# power_amp.net
KiCad netlist of a schematic drawn in Altium Designer
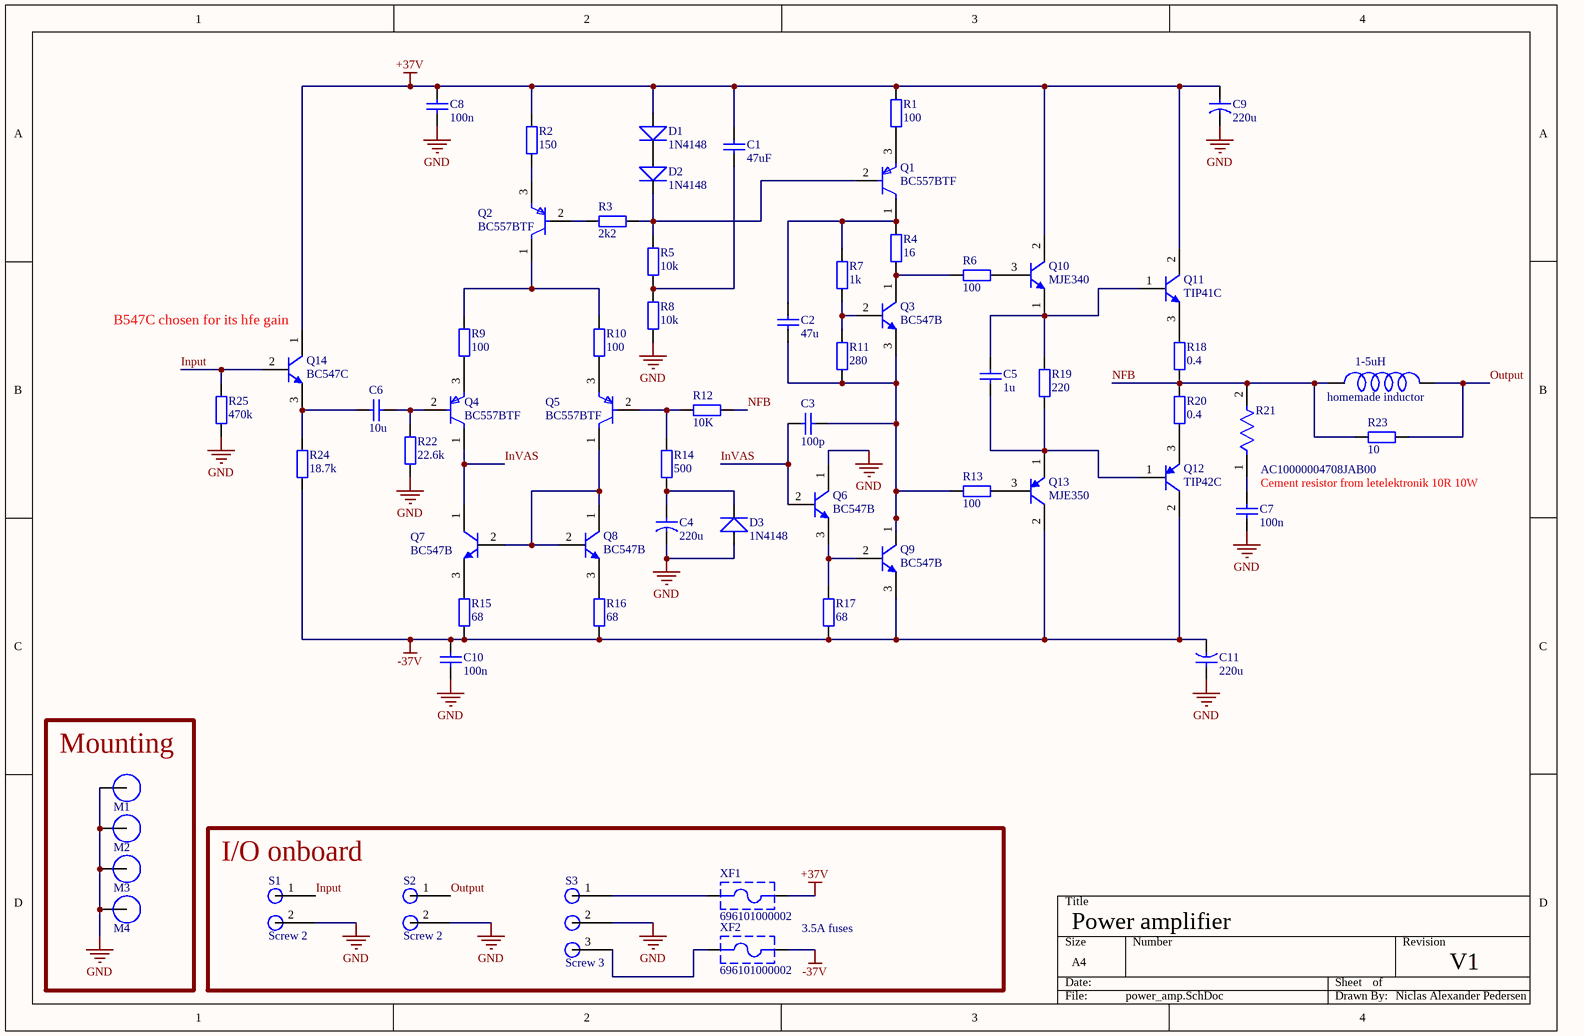
[diagram p0: power_amp.SchDoc]

(export (version "E")
  (design (tool "Eeschema 10.0.6"))
  (components
    (comp (ref "1-5uH")
      (value "homemade inductor")
      (footprint "homecooked inductor")
      (libsource (lib "esd410") (part "homemade inductor"))
    )
    (comp (ref "C1")
      (value "47uF")
      (footprint "Cap Ø8")
      (fields (field (name "Comment") "Cap"))
      (libsource (lib "AAURacing") (part "Capacitor unpolarized"))
    )
    (comp (ref "C2")
      (value "47u")
      (footprint "Cap Ø8")
      (fields (field (name "Comment") "Cap"))
      (libsource (lib "AAURacing") (part "Capacitor unpolarized"))
    )
    (comp (ref "C3")
      (value "100p")
      (footprint "Cap-1")
      (fields (field (name "Comment") "Cap"))
      (libsource (lib "AAURacing") (part "Capacitor 1 space"))
    )
    (comp (ref "C4")
      (value "220u")
      (footprint "Cap Lyt Ø8")
      (fields (field (name "Comment") "Cap"))
      (libsource (lib "AAURacing") (part "Capacitor electrolytic"))
    )
    (comp (ref "C5")
      (value "1u")
      (footprint "Cap Ø8")
      (fields (field (name "Comment") "Cap"))
      (libsource (lib "AAURacing") (part "Capacitor unpolarized"))
    )
    (comp (ref "C6")
      (value "10u")
      (footprint "Cap Ø8")
      (fields (field (name "Comment") "Cap"))
      (libsource (lib "AAURacing") (part "Capacitor unpolarized"))
    )
    (comp (ref "C7")
      (value "100n")
      (footprint "Cap Ø8")
      (fields (field (name "Comment") "Cap"))
      (libsource (lib "AAURacing") (part "Capacitor unpolarized"))
    )
    (comp (ref "C8")
      (value "100n")
      (footprint "Cap-1")
      (fields (field (name "Comment") "Cap"))
      (libsource (lib "AAURacing") (part "Capacitor 1 space"))
    )
    (comp (ref "C9")
      (value "220u")
      (footprint "Cap Lyt Ø8")
      (fields (field (name "Comment") "Cap"))
      (libsource (lib "AAURacing") (part "Capacitor electrolytic"))
    )
    (comp (ref "C10")
      (value "100n")
      (footprint "Cap-1")
      (fields (field (name "Comment") "Cap"))
      (libsource (lib "AAURacing") (part "Capacitor 1 space"))
    )
    (comp (ref "C11")
      (value "220u")
      (footprint "Cap Lyt Ø8")
      (fields (field (name "Comment") "Cap"))
      (libsource (lib "AAURacing") (part "Capacitor electrolytic"))
    )
    (comp (ref "D1")
      (value "Diode DO-35")
      (footprint "Diode 2 space")
      (fields (field (name "MODEL") "1N4148"))
      (libsource (lib "AAURacing") (part "Diode DO-35"))
    )
    (comp (ref "D2")
      (value "Diode DO-35")
      (footprint "Diode 2 space")
      (fields (field (name "MODEL") "1N4148"))
      (libsource (lib "AAURacing") (part "Diode DO-35"))
    )
    (comp (ref "D3")
      (value "Diode DO-35")
      (footprint "Diode 2 space")
      (fields (field (name "MODEL") "1N4148"))
      (libsource (lib "AAURacing") (part "Diode DO-35"))
    )
    (comp (ref "M1")
      (value "Screw Hole")
      (footprint "M3 Hole")
      (libsource (lib "AAURacing") (part "Screw Hole"))
    )
    (comp (ref "M2")
      (value "Screw Hole")
      (footprint "M3 Hole")
      (libsource (lib "AAURacing") (part "Screw Hole"))
    )
    (comp (ref "M3")
      (value "Screw Hole")
      (footprint "M3 Hole")
      (libsource (lib "AAURacing") (part "Screw Hole"))
    )
    (comp (ref "M4")
      (value "Screw Hole")
      (footprint "M3 Hole")
      (libsource (lib "AAURacing") (part "Screw Hole"))
    )
    (comp (ref "Q1")
      (value "BC557BTF")
      (footprint "FP-135AR-MFG")
      (description "BC557BTF Small Signal Bipolar Transistor, 0.1A I(C), 45V V(BR)CEO, 1-Element, PNP, Silicon, TO-92")
      (libsource (lib "Altium Content Vault") (part "9e2844d3eb996af6824d2c99fe21afc"))
    )
    (comp (ref "Q2")
      (value "BC557BTF")
      (footprint "FP-135AR-MFG")
      (description "BC557BTF Small Signal Bipolar Transistor, 0.1A I(C), 45V V(BR)CEO, 1-Element, PNP, Silicon, TO-92")
      (libsource (lib "Altium Content Vault") (part "9e2844d3eb996af6824d2c99fe21afc"))
    )
    (comp (ref "Q3")
      (value "BC547B")
      (footprint "ONSC-TO-92-3-29-11")
      (description "Amplifier Transistor, NPN Silicon, 3-Pin TO-92, Bulk Box")
      (fields (field (name "MANUFACTURER") "On Semiconductor"))
      (libsource (lib "Altium Content Vault") (part "ONSC-NPN-C1B2E3-3"))
    )
    (comp (ref "Q4")
      (value "BC557BTF")
      (footprint "FP-135AR-MFG")
      (description "BC557BTF Small Signal Bipolar Transistor, 0.1A I(C), 45V V(BR)CEO, 1-Element, PNP, Silicon, TO-92")
      (libsource (lib "Altium Content Vault") (part "9e2844d3eb996af6824d2c99fe21afc"))
    )
    (comp (ref "Q5")
      (value "BC557BTF")
      (footprint "FP-135AR-MFG")
      (description "BC557BTF Small Signal Bipolar Transistor, 0.1A I(C), 45V V(BR)CEO, 1-Element, PNP, Silicon, TO-92")
      (libsource (lib "Altium Content Vault") (part "9e2844d3eb996af6824d2c99fe21afc"))
    )
    (comp (ref "Q6")
      (value "BC547B")
      (footprint "ONSC-TO-92-3-29-11")
      (description "Amplifier Transistor, NPN Silicon, 3-Pin TO-92, Bulk Box")
      (fields (field (name "MANUFACTURER") "On Semiconductor"))
      (libsource (lib "Altium Content Vault") (part "ONSC-NPN-C1B2E3-3"))
    )
    (comp (ref "Q7")
      (value "BC547B")
      (footprint "ONSC-TO-92-3-29-11")
      (description "Amplifier Transistor, NPN Silicon, 3-Pin TO-92, Bulk Box")
      (fields (field (name "MANUFACTURER") "On Semiconductor"))
      (libsource (lib "Altium Content Vault") (part "ONSC-NPN-C1B2E3-3"))
    )
    (comp (ref "Q8")
      (value "BC547B")
      (footprint "ONSC-TO-92-3-29-11")
      (description "Amplifier Transistor, NPN Silicon, 3-Pin TO-92, Bulk Box")
      (fields (field (name "MANUFACTURER") "On Semiconductor"))
      (libsource (lib "Altium Content Vault") (part "ONSC-NPN-C1B2E3-3"))
    )
    (comp (ref "Q9")
      (value "BC547B")
      (footprint "ONSC-TO-92-3-29-11")
      (description "Amplifier Transistor, NPN Silicon, 3-Pin TO-92, Bulk Box")
      (fields (field (name "MANUFACTURER") "On Semiconductor"))
      (libsource (lib "Altium Content Vault") (part "ONSC-NPN-C1B2E3-3"))
    )
    (comp (ref "Q10")
      (value "MJE340")
      (footprint "ONSC-TO-225-3-77-09")
      (description "Plastic Medium-Power NPN Silicon Transistor, 3-Pin TO-225, Bulk Box")
      (fields (field (name "MANUFACTURER") "On Semiconductor"))
      (libsource (lib "Altium Content Vault") (part "ONSC-NPN-E1C2B3-3"))
    )
    (comp (ref "Q11")
      (value "TIP41C")
      (footprint "ONSC-TO-220-3-221A-09")
      (description "Complementary Silicon Plastic Power Transistor, 3-Pin TO-220, Tube")
      (fields (field (name "MANUFACTURER") "On Semiconductor"))
      (libsource (lib "Altium Content Vault") (part "ONSC-NPN-B1C2E3-3_C"))
    )
    (comp (ref "Q12")
      (value "TIP42C")
      (footprint "ONSC-TO-220-3-221A-09")
      (description "Complementary Silicon Plastic Power Transistor, 3-Pin TO-220, Tube")
      (fields (field (name "MANUFACTURER") "On Semiconductor"))
      (libsource (lib "Altium Content Vault") (part "ONSC-PNP-B1C2E3-3"))
    )
    (comp (ref "Q13")
      (value "MJE350")
      (footprint "ONSC-TO-225-3-77-09")
      (description "Plastic Medium-Power PNP Silicon Transistor, 3-Pin TO-225, Bulk Box")
      (fields (field (name "MANUFACTURER") "On Semiconductor"))
      (libsource (lib "Altium Content Vault") (part "ONSC-PNP-E1C2B3-3"))
    )
    (comp (ref "Q14")
      (value "BC547C")
      (footprint "ONSC-TO-92-3-29-11")
      (description "Amplifier Transistor, NPN Silicon, 3-Pin TO-92, Bulk Box")
      (fields (field (name "MANUFACTURER") "On Semiconductor") (field (name "PARTNUMBER") "BC547B"))
      (libsource (lib "Altium Content Vault") (part "ONSC-NPN-C1B2E3-3"))
    )
    (comp (ref "R1")
      (value "100")
      (footprint "RES THT 9mm")
      (fields (field (name "Comment") "Resistor"))
      (libsource (lib "AAURacing") (part "Resistor"))
    )
    (comp (ref "R2")
      (value "150")
      (footprint "RES THT 9mm")
      (fields (field (name "Comment") "Resistor"))
      (libsource (lib "AAURacing") (part "Resistor"))
    )
    (comp (ref "R3")
      (value "2k2")
      (footprint "RES THT 9mm")
      (fields (field (name "Comment") "Resistor"))
      (libsource (lib "AAURacing") (part "Resistor"))
    )
    (comp (ref "R4")
      (value "16")
      (footprint "RES THT 9mm")
      (fields (field (name "Comment") "Resistor"))
      (libsource (lib "AAURacing") (part "Resistor"))
    )
    (comp (ref "R5")
      (value "10k")
      (footprint "RES THT 9mm")
      (fields (field (name "Comment") "Resistor"))
      (libsource (lib "AAURacing") (part "Resistor"))
    )
    (comp (ref "R6")
      (value "100")
      (footprint "RES THT 9mm")
      (fields (field (name "Comment") "Resistor"))
      (libsource (lib "AAURacing") (part "Resistor"))
    )
    (comp (ref "R7")
      (value "1k")
      (footprint "RES THT 9mm")
      (fields (field (name "Comment") "Resistor"))
      (libsource (lib "AAURacing") (part "Resistor"))
    )
    (comp (ref "R8")
      (value "10k")
      (footprint "RES THT 9mm")
      (fields (field (name "Comment") "Resistor"))
      (libsource (lib "AAURacing") (part "Resistor"))
    )
    (comp (ref "R9")
      (value "100")
      (footprint "RES THT 9mm")
      (fields (field (name "Comment") "Resistor"))
      (libsource (lib "AAURacing") (part "Resistor"))
    )
    (comp (ref "R10")
      (value "100")
      (footprint "RES THT 9mm")
      (fields (field (name "Comment") "Resistor"))
      (libsource (lib "AAURacing") (part "Resistor"))
    )
    (comp (ref "R11")
      (value "280")
      (footprint "RES THT 9mm")
      (fields (field (name "Comment") "Resistor"))
      (libsource (lib "AAURacing") (part "Resistor"))
    )
    (comp (ref "R12")
      (value "10K")
      (footprint "RES THT 9mm")
      (fields (field (name "Comment") "Resistor"))
      (libsource (lib "AAURacing") (part "Resistor"))
    )
    (comp (ref "R13")
      (value "100")
      (footprint "RES THT 9mm")
      (fields (field (name "Comment") "Resistor"))
      (libsource (lib "AAURacing") (part "Resistor"))
    )
    (comp (ref "R14")
      (value "500")
      (footprint "RES THT 9mm")
      (fields (field (name "Comment") "Resistor"))
      (libsource (lib "AAURacing") (part "Resistor"))
    )
    (comp (ref "R15")
      (value "68")
      (footprint "RES THT 9mm")
      (fields (field (name "Comment") "Resistor"))
      (libsource (lib "AAURacing") (part "Resistor"))
    )
    (comp (ref "R16")
      (value "68")
      (footprint "RES THT 9mm")
      (fields (field (name "Comment") "Resistor"))
      (libsource (lib "AAURacing") (part "Resistor"))
    )
    (comp (ref "R17")
      (value "68")
      (footprint "RES THT 9mm")
      (fields (field (name "Comment") "Resistor"))
      (libsource (lib "AAURacing") (part "Resistor"))
    )
    (comp (ref "R18")
      (value "0.4")
      (footprint "RES THT 30mm")
      (fields (field (name "Comment") "Resistor"))
      (libsource (lib "AAURacing") (part "Resistor"))
    )
    (comp (ref "R19")
      (value "220")
      (footprint "RES THT 9mm")
      (fields (field (name "Comment") "Resistor"))
      (libsource (lib "AAURacing") (part "Resistor"))
    )
    (comp (ref "R20")
      (value "0.4")
      (footprint "RES THT 30mm")
      (fields (field (name "Comment") "Resistor"))
      (libsource (lib "AAURacing") (part "Resistor"))
    )
    (comp (ref "R21")
      (value "AC10000004708JAB00")
      (footprint "FP-AC10-MFG")
      (description "AC10000004708JAB00 Resistor, 4.7 Ohm, ± 5%, 10 W, Axial Leaded, Wirewound, General Purpose")
      (fields (field (name "TOLERANCE") "5%"))
      (libsource (lib "Altium Content Vault") (part "1029c3af85768c4190bb7ad29bc67b5"))
    )
    (comp (ref "R22")
      (value "22.6k")
      (footprint "RES THT 9mm")
      (fields (field (name "Comment") "Resistor"))
      (libsource (lib "AAURacing") (part "Resistor"))
    )
    (comp (ref "R23")
      (value "10")
      (footprint "RES THT 9mm")
      (fields (field (name "Comment") "Resistor"))
      (libsource (lib "AAURacing") (part "Resistor"))
    )
    (comp (ref "R24")
      (value "18.7k")
      (footprint "RES THT 9mm")
      (fields (field (name "Comment") "Resistor"))
      (libsource (lib "AAURacing") (part "Resistor"))
    )
    (comp (ref "R25")
      (value "470k")
      (footprint "RES THT 9mm")
      (fields (field (name "Comment") "Resistor"))
      (libsource (lib "AAURacing") (part "Resistor"))
    )
    (comp (ref "S1") (value "Screw 2") (footprint "Screw-2") (libsource (lib "AAURacing") (part "Screw 2")))
    (comp (ref "S2") (value "Screw 2") (footprint "Screw-2") (libsource (lib "AAURacing") (part "Screw 2")))
    (comp (ref "S3") (value "Screw 3") (footprint "Screw-3") (libsource (lib "AAURacing") (part "Screw 3")))
    (comp (ref "XF1")
      (value "696101000002")
      (footprint "696101000002")
      (libsource (lib "Altium Content Vault") (part "Fuse Holder"))
    )
    (comp (ref "XF2")
      (value "696101000002")
      (footprint "696101000002")
      (libsource (lib "Altium Content Vault") (part "Fuse Holder"))
    )
  )
  (nets
    (net (code "1") (name "+37V") (class "Default")
      (node (ref "C1") (pin "2") (pinfunction "g_2") (pintype "passive"))
      (node (ref "C8") (pin "2") (pinfunction "g_2") (pintype "passive"))
      (node (ref "C9") (pin "1") (pinfunction "1_1") (pintype "passive"))
      (node (ref "D1") (pin "1") (pinfunction "1_1") (pintype "passive"))
      (node (ref "Q10") (pin "2") (pinfunction "C_2") (pintype "passive"))
      (node (ref "Q11") (pin "2") (pinfunction "C_2") (pintype "passive"))
      (node (ref "Q14") (pin "1") (pinfunction "C_1") (pintype "passive"))
      (node (ref "R1") (pin "2") (pinfunction "2_2") (pintype "passive"))
      (node (ref "R2") (pin "2") (pinfunction "2_2") (pintype "passive"))
      (node (ref "XF1") (pin "2") (pinfunction "2_2") (pintype "passive"))
    )
    (net (code "2") (name "-37V") (class "Default")
      (node (ref "C10") (pin "2") (pinfunction "g_2") (pintype "passive"))
      (node (ref "C11") (pin "2") (pinfunction "g_2") (pintype "passive"))
      (node (ref "Q12") (pin "2") (pinfunction "C_2") (pintype "passive"))
      (node (ref "Q13") (pin "2") (pinfunction "C_2") (pintype "passive"))
      (node (ref "Q9") (pin "3") (pinfunction "E_3") (pintype "passive"))
      (node (ref "R15") (pin "1") (pinfunction "1_1") (pintype "passive"))
      (node (ref "R16") (pin "1") (pinfunction "1_1") (pintype "passive"))
      (node (ref "R17") (pin "1") (pinfunction "1_1") (pintype "passive"))
      (node (ref "R24") (pin "2") (pinfunction "2_2") (pintype "passive"))
      (node (ref "XF2") (pin "2") (pinfunction "2_2") (pintype "passive"))
    )
    (net (code "3") (name "/InVAS") (class "Default")
      (node (ref "C3") (pin "1") (pinfunction "1_1") (pintype "passive"))
      (node (ref "Q4") (pin "1") (pinfunction "C_1") (pintype "passive"))
      (node (ref "Q6") (pin "2") (pinfunction "B_2") (pintype "passive"))
      (node (ref "Q7") (pin "1") (pinfunction "C_1") (pintype "passive"))
    )
    (net (code "4") (name "/Input") (class "Default")
      (node (ref "Q14") (pin "2") (pinfunction "B_2") (pintype "passive"))
      (node (ref "R25") (pin "2") (pinfunction "2_2") (pintype "passive"))
      (node (ref "S1") (pin "1") (pinfunction "1_1") (pintype "passive"))
    )
    (net (code "5") (name "/NFB") (class "Default")
      (node (ref "1-5uH") (pin "1") (pintype "passive"))
      (node (ref "R12") (pin "1") (pinfunction "1_1") (pintype "passive"))
      (node (ref "R18") (pin "1") (pinfunction "1_1") (pintype "passive"))
      (node (ref "R20") (pin "2") (pinfunction "2_2") (pintype "passive"))
      (node (ref "R21") (pin "2") (pinfunction "2_2") (pintype "passive"))
      (node (ref "R23") (pin "2") (pinfunction "2_2") (pintype "passive"))
    )
    (net (code "6") (name "/Output") (class "Default")
      (node (ref "1-5uH") (pin "2") (pintype "passive"))
      (node (ref "R23") (pin "1") (pinfunction "1_1") (pintype "passive"))
      (node (ref "S2") (pin "1") (pinfunction "1_1") (pintype "passive"))
    )
    (net (code "7") (name "GND") (class "Default")
      (node (ref "C10") (pin "1") (pinfunction "1_1") (pintype "passive"))
      (node (ref "C11") (pin "1") (pinfunction "1_1") (pintype "passive"))
      (node (ref "C4") (pin "2") (pinfunction "g_2") (pintype "passive"))
      (node (ref "C7") (pin "1") (pinfunction "1_1") (pintype "passive"))
      (node (ref "C8") (pin "1") (pinfunction "1_1") (pintype "passive"))
      (node (ref "C9") (pin "2") (pinfunction "g_2") (pintype "passive"))
      (node (ref "D3") (pin "1") (pinfunction "1_1") (pintype "passive"))
      (node (ref "M1") (pin "1") (pinfunction "1_1") (pintype "passive"))
      (node (ref "M2") (pin "1") (pinfunction "1_1") (pintype "passive"))
      (node (ref "M3") (pin "1") (pinfunction "1_1") (pintype "passive"))
      (node (ref "M4") (pin "1") (pinfunction "1_1") (pintype "passive"))
      (node (ref "Q6") (pin "1") (pinfunction "C_1") (pintype "passive"))
      (node (ref "R22") (pin "2") (pinfunction "2_2") (pintype "passive"))
      (node (ref "R25") (pin "1") (pinfunction "1_1") (pintype "passive"))
      (node (ref "R8") (pin "2") (pinfunction "2_2") (pintype "passive"))
      (node (ref "S1") (pin "2") (pinfunction "2_2") (pintype "passive"))
      (node (ref "S2") (pin "2") (pinfunction "2_2") (pintype "passive"))
      (node (ref "S3") (pin "2") (pinfunction "2_2") (pintype "passive"))
    )
    (net (code "8") (name "Net-(C1-Pad1)") (class "Default")
      (node (ref "C1") (pin "1") (pinfunction "1_1") (pintype "passive"))
      (node (ref "R5") (pin "2") (pinfunction "2_2") (pintype "passive"))
      (node (ref "R8") (pin "1") (pinfunction "1_1") (pintype "passive"))
    )
    (net (code "9") (name "Net-(C2-g)") (class "Default")
      (node (ref "C2") (pin "2") (pinfunction "g_2") (pintype "passive"))
      (node (ref "Q1") (pin "1") (pinfunction "C_1") (pintype "passive"))
      (node (ref "R4") (pin "2") (pinfunction "2_2") (pintype "passive"))
      (node (ref "R7") (pin "2") (pinfunction "2_2") (pintype "passive"))
    )
    (net (code "10") (name "Net-(C3-g)") (class "Default")
      (node (ref "C2") (pin "1") (pinfunction "1_1") (pintype "passive"))
      (node (ref "C3") (pin "2") (pinfunction "g_2") (pintype "passive"))
      (node (ref "Q3") (pin "3") (pinfunction "E_3") (pintype "passive"))
      (node (ref "Q9") (pin "1") (pinfunction "C_1") (pintype "passive"))
      (node (ref "R11") (pin "1") (pinfunction "1_1") (pintype "passive"))
      (node (ref "R13") (pin "2") (pinfunction "2_2") (pintype "passive"))
    )
    (net (code "11") (name "Net-(C4-Pad1)") (class "Default")
      (node (ref "C4") (pin "1") (pinfunction "1_1") (pintype "passive"))
      (node (ref "D3") (pin "2") (pinfunction "2_2") (pintype "passive"))
      (node (ref "R14") (pin "1") (pinfunction "1_1") (pintype "passive"))
    )
    (net (code "12") (name "Net-(C5-g)") (class "Default")
      (node (ref "C5") (pin "2") (pinfunction "g_2") (pintype "passive"))
      (node (ref "Q10") (pin "1") (pinfunction "E_1") (pintype "passive"))
      (node (ref "Q11") (pin "1") (pinfunction "B_1") (pintype "passive"))
      (node (ref "R19") (pin "2") (pinfunction "2_2") (pintype "passive"))
    )
    (net (code "13") (name "Net-(C6-g)") (class "Default")
      (node (ref "C6") (pin "2") (pinfunction "g_2") (pintype "passive"))
      (node (ref "Q14") (pin "3") (pinfunction "E_3") (pintype "passive"))
      (node (ref "R24") (pin "1") (pinfunction "1_1") (pintype "passive"))
    )
    (net (code "14") (name "Net-(C7-g)") (class "Default")
      (node (ref "C7") (pin "2") (pinfunction "g_2") (pintype "passive"))
      (node (ref "R21") (pin "1") (pinfunction "1_1") (pintype "passive"))
    )
    (net (code "15") (name "Net-(D1-Pad2)") (class "Default")
      (node (ref "D1") (pin "2") (pinfunction "2_2") (pintype "passive"))
      (node (ref "D2") (pin "1") (pinfunction "1_1") (pintype "passive"))
    )
    (net (code "16") (name "Net-(Q1-B)") (class "Default")
      (node (ref "D2") (pin "2") (pinfunction "2_2") (pintype "passive"))
      (node (ref "Q1") (pin "2") (pinfunction "B_2") (pintype "passive"))
      (node (ref "R3") (pin "1") (pinfunction "1_1") (pintype "passive"))
      (node (ref "R5") (pin "1") (pinfunction "1_1") (pintype "passive"))
    )
    (net (code "17") (name "Net-(Q1-E)") (class "Default")
      (node (ref "Q1") (pin "3") (pinfunction "E_3") (pintype "passive"))
      (node (ref "R1") (pin "1") (pinfunction "1_1") (pintype "passive"))
    )
    (net (code "18") (name "Net-(Q2-B)") (class "Default")
      (node (ref "Q2") (pin "2") (pinfunction "B_2") (pintype "passive"))
      (node (ref "R3") (pin "2") (pinfunction "2_2") (pintype "passive"))
    )
    (net (code "19") (name "Net-(Q2-C)") (class "Default")
      (node (ref "Q2") (pin "1") (pinfunction "C_1") (pintype "passive"))
      (node (ref "R10") (pin "2") (pinfunction "2_2") (pintype "passive"))
      (node (ref "R9") (pin "2") (pinfunction "2_2") (pintype "passive"))
    )
    (net (code "20") (name "Net-(Q2-E)") (class "Default")
      (node (ref "Q2") (pin "3") (pinfunction "E_3") (pintype "passive"))
      (node (ref "R2") (pin "1") (pinfunction "1_1") (pintype "passive"))
    )
    (net (code "21") (name "Net-(Q3-B)") (class "Default")
      (node (ref "Q3") (pin "2") (pinfunction "B_2") (pintype "passive"))
      (node (ref "R11") (pin "2") (pinfunction "2_2") (pintype "passive"))
      (node (ref "R7") (pin "1") (pinfunction "1_1") (pintype "passive"))
    )
    (net (code "22") (name "Net-(Q3-C)") (class "Default")
      (node (ref "Q3") (pin "1") (pinfunction "C_1") (pintype "passive"))
      (node (ref "R4") (pin "1") (pinfunction "1_1") (pintype "passive"))
      (node (ref "R6") (pin "2") (pinfunction "2_2") (pintype "passive"))
    )
    (net (code "23") (name "Net-(Q4-B)") (class "Default")
      (node (ref "C6") (pin "1") (pinfunction "1_1") (pintype "passive"))
      (node (ref "Q4") (pin "2") (pinfunction "B_2") (pintype "passive"))
      (node (ref "R22") (pin "1") (pinfunction "1_1") (pintype "passive"))
    )
    (net (code "24") (name "Net-(Q4-E)") (class "Default")
      (node (ref "Q4") (pin "3") (pinfunction "E_3") (pintype "passive"))
      (node (ref "R9") (pin "1") (pinfunction "1_1") (pintype "passive"))
    )
    (net (code "25") (name "Net-(Q5-B)") (class "Default")
      (node (ref "Q5") (pin "2") (pinfunction "B_2") (pintype "passive"))
      (node (ref "R12") (pin "2") (pinfunction "2_2") (pintype "passive"))
      (node (ref "R14") (pin "2") (pinfunction "2_2") (pintype "passive"))
    )
    (net (code "26") (name "Net-(Q5-C)") (class "Default")
      (node (ref "Q5") (pin "1") (pinfunction "C_1") (pintype "passive"))
      (node (ref "Q7") (pin "2") (pinfunction "B_2") (pintype "passive"))
      (node (ref "Q8") (pin "1") (pinfunction "C_1") (pintype "passive"))
      (node (ref "Q8") (pin "2") (pinfunction "B_2") (pintype "passive"))
    )
    (net (code "27") (name "Net-(Q5-E)") (class "Default")
      (node (ref "Q5") (pin "3") (pinfunction "E_3") (pintype "passive"))
      (node (ref "R10") (pin "1") (pinfunction "1_1") (pintype "passive"))
    )
    (net (code "28") (name "Net-(Q6-E)") (class "Default")
      (node (ref "Q6") (pin "3") (pinfunction "E_3") (pintype "passive"))
      (node (ref "Q9") (pin "2") (pinfunction "B_2") (pintype "passive"))
      (node (ref "R17") (pin "2") (pinfunction "2_2") (pintype "passive"))
    )
    (net (code "29") (name "Net-(Q7-E)") (class "Default")
      (node (ref "Q7") (pin "3") (pinfunction "E_3") (pintype "passive"))
      (node (ref "R15") (pin "2") (pinfunction "2_2") (pintype "passive"))
    )
    (net (code "30") (name "Net-(Q8-E)") (class "Default")
      (node (ref "Q8") (pin "3") (pinfunction "E_3") (pintype "passive"))
      (node (ref "R16") (pin "2") (pinfunction "2_2") (pintype "passive"))
    )
    (net (code "31") (name "Net-(Q10-B)") (class "Default")
      (node (ref "Q10") (pin "3") (pinfunction "B_3") (pintype "passive"))
      (node (ref "R6") (pin "1") (pinfunction "1_1") (pintype "passive"))
    )
    (net (code "32") (name "Net-(Q11-E)") (class "Default")
      (node (ref "Q11") (pin "3") (pinfunction "E_3") (pintype "passive"))
      (node (ref "R18") (pin "2") (pinfunction "2_2") (pintype "passive"))
    )
    (net (code "33") (name "Net-(Q12-B)") (class "Default")
      (node (ref "C5") (pin "1") (pinfunction "1_1") (pintype "passive"))
      (node (ref "Q12") (pin "1") (pinfunction "B_1") (pintype "passive"))
      (node (ref "Q13") (pin "1") (pinfunction "E_1") (pintype "passive"))
      (node (ref "R19") (pin "1") (pinfunction "1_1") (pintype "passive"))
    )
    (net (code "34") (name "Net-(Q12-E)") (class "Default")
      (node (ref "Q12") (pin "3") (pinfunction "E_3") (pintype "passive"))
      (node (ref "R20") (pin "1") (pinfunction "1_1") (pintype "passive"))
    )
    (net (code "35") (name "Net-(Q13-B)") (class "Default")
      (node (ref "Q13") (pin "3") (pinfunction "B_3") (pintype "passive"))
      (node (ref "R13") (pin "1") (pinfunction "1_1") (pintype "passive"))
    )
    (net (code "36") (name "Net-(S3-Pad1)") (class "Default")
      (node (ref "S3") (pin "1") (pinfunction "1_1") (pintype "passive"))
      (node (ref "XF1") (pin "1") (pinfunction "1_1") (pintype "passive"))
    )
    (net (code "37") (name "Net-(S3-Pad3)") (class "Default")
      (node (ref "S3") (pin "3") (pinfunction "3_3") (pintype "passive"))
      (node (ref "XF2") (pin "1") (pinfunction "1_1") (pintype "passive"))
    )
  )
)
